# Rail_Shutdown_AD.net
KiCad netlist of a schematic drawn in Altium Designer
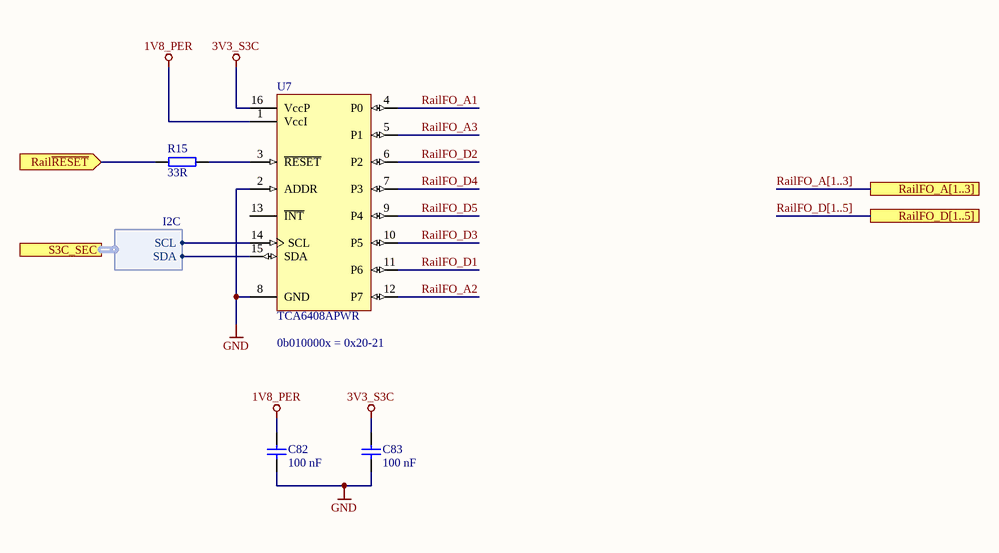
[diagram p0: Rail_Shutdown_AD.SchDoc]

(export (version "E")
  (design (tool "Eeschema 10.0.6"))
  (components
    (comp (ref "C82")
      (value "100 nF")
      (footprint "C_0603_TE")
      (description "Generic capacitor")
      (fields
        (field (name "MANUFACTURER PART NUMBER") "UZgen_C_0603_100nF_50V_X7R")
        (field (name "MANUFACTURER") "UZgen")
        (field (name "CREATED FROM") "AGeiger")
      )
      (libsource (lib "user") (part "CAP-NP"))
    )
    (comp (ref "C83")
      (value "100 nF")
      (footprint "C_0603_TE")
      (description "Generic capacitor")
      (fields
        (field (name "MANUFACTURER PART NUMBER") "UZgen_C_0603_100nF_50V_X7R")
        (field (name "MANUFACTURER") "UZgen")
        (field (name "CREATED FROM") "AGeiger")
      )
      (libsource (lib "user") (part "CAP-NP"))
    )
    (comp (ref "R15")
      (value "33R")
      (footprint "R_0603_TE")
      (description "Generic resistor")
      (fields
        (field (name "MANUFACTURER PART NUMBER") "UZgen_R_0603_33R")
        (field (name "MANUFACTURER") "UZgen")
        (field (name "CREATED FROM") "UZgenTool")
      )
      (libsource (lib "user") (part "RES"))
    )
    (comp (ref "U7")
      (value "TCA6408APWR")
      (footprint "TSSOP-16_PW0016A_N")
      (fields
        (field (name "MANUFACTURER") "Texas Instruments")
        (field (name "LCSC PART NUMBER") "C206177")
        (field (name "CREATED FROM") "MGeier")
      )
      (libsource (lib "user") (part "TCA6408APWR"))
    )
  )
  (nets
    (net (code "2") (name "/RailFO_A1") (class "Default")
      (node (ref "U7") (pin "4") (pinfunction "P0_4") (pintype "bidirectional"))
    )
    (net (code "3") (name "/RailFO_A2") (class "Default")
      (node (ref "U7") (pin "12") (pinfunction "P7_12") (pintype "bidirectional"))
    )
    (net (code "4") (name "/RailFO_A3") (class "Default")
      (node (ref "U7") (pin "5") (pinfunction "P1_5") (pintype "bidirectional"))
    )
    (net (code "6") (name "/RailFO_D1") (class "Default")
      (node (ref "U7") (pin "11") (pinfunction "P6_11") (pintype "bidirectional"))
    )
    (net (code "7") (name "/RailFO_D2") (class "Default")
      (node (ref "U7") (pin "6") (pinfunction "P2_6") (pintype "bidirectional"))
    )
    (net (code "8") (name "/RailFO_D3") (class "Default")
      (node (ref "U7") (pin "10") (pinfunction "P5_10") (pintype "bidirectional"))
    )
    (net (code "9") (name "/RailFO_D4") (class "Default")
      (node (ref "U7") (pin "7") (pinfunction "P3_7") (pintype "bidirectional"))
    )
    (net (code "10") (name "/RailFO_D5") (class "Default")
      (node (ref "U7") (pin "9") (pinfunction "P4_9") (pintype "bidirectional"))
    )
    (net (code "12") (name "/Rail~{RESET}") (class "Default")
      (node (ref "R15") (pin "1") (pinfunction "1_1") (pintype "passive"))
    )
    (net (code "13") (name "/SCL") (class "Default")
      (node (ref "U7") (pin "14") (pinfunction "SCL_14") (pintype "input"))
    )
    (net (code "14") (name "/SDA") (class "Default")
      (node (ref "U7") (pin "15") (pinfunction "SDA_15") (pintype "bidirectional"))
    )
    (net (code "16") (name "1V8_PER") (class "Default")
      (node (ref "C82") (pin "1") (pinfunction "1_1") (pintype "passive"))
      (node (ref "U7") (pin "1") (pinfunction "VccI_1") (pintype "power_in"))
    )
    (net (code "17") (name "3V3_S3C") (class "Default")
      (node (ref "C83") (pin "1") (pinfunction "1_1") (pintype "passive"))
      (node (ref "U7") (pin "16") (pinfunction "VccP_16") (pintype "power_in"))
    )
    (net (code "18") (name "GND") (class "Default")
      (node (ref "C82") (pin "2") (pinfunction "2_2") (pintype "passive"))
      (node (ref "C83") (pin "2") (pinfunction "2_2") (pintype "passive"))
      (node (ref "U7") (pin "2") (pinfunction "ADDR_2") (pintype "input"))
      (node (ref "U7") (pin "8") (pinfunction "GND_8") (pintype "power_in"))
    )
    (net (code "19") (name "Net-(U7-~{RESET})") (class "Default")
      (node (ref "R15") (pin "2") (pinfunction "2_2") (pintype "passive"))
      (node (ref "U7") (pin "3") (pinfunction "~{RESET}_3") (pintype "input"))
    )
    (net (code "20") (name "unconnected-(U7-~{INT}-Pad13)") (class "Default")
      (node (ref "U7") (pin "13") (pinfunction "~{INT}_13") (pintype "open_collector"))
    )
  )
)
